# I2C_Keypad_host_module.net
KiCad netlist of a schematic drawn in Altium Designer
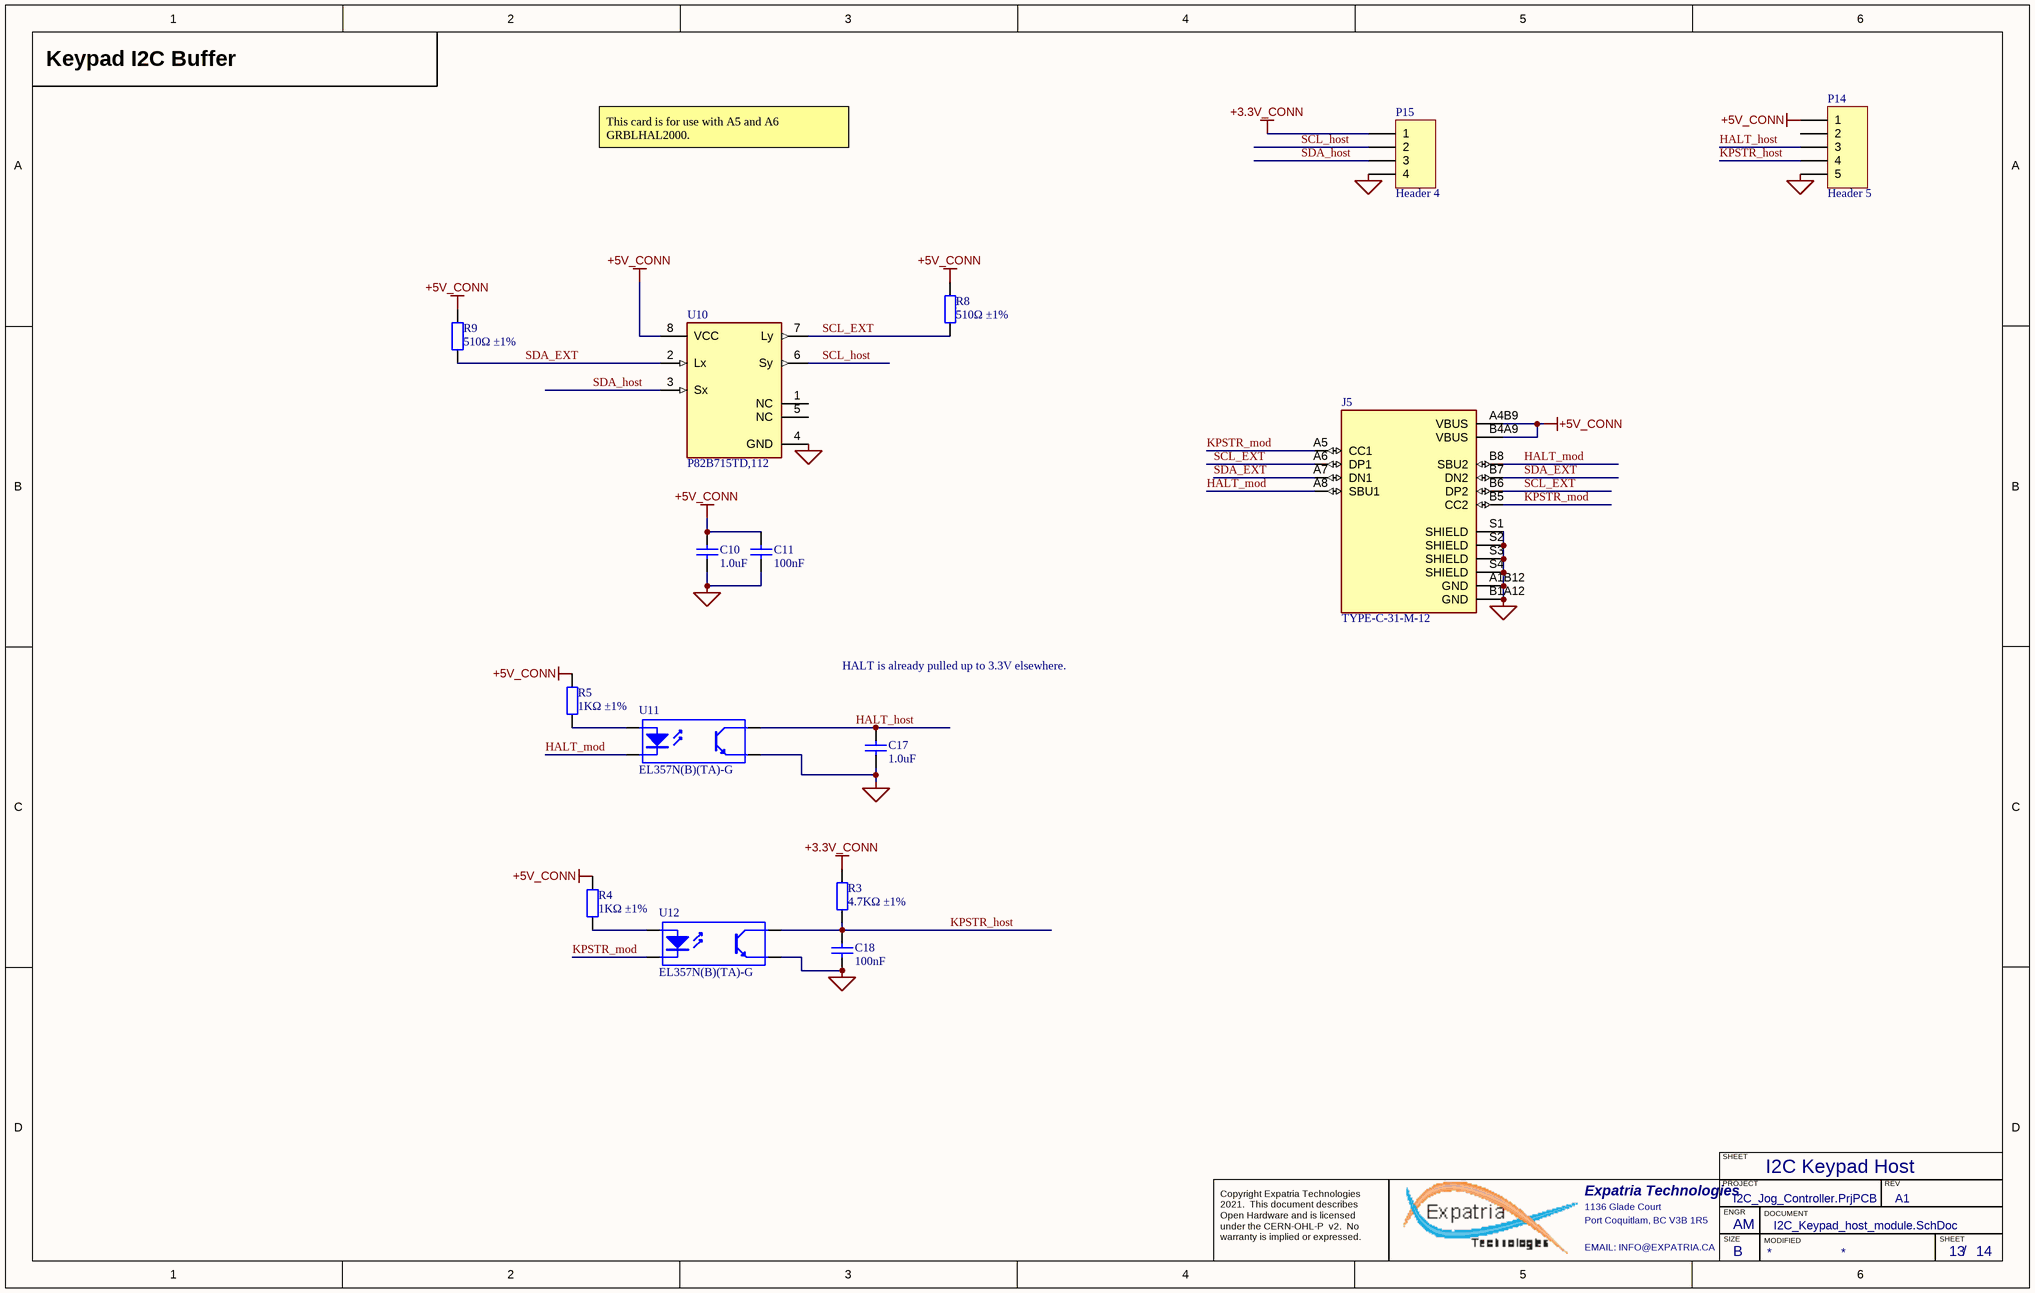
[diagram p0: I2C_Keypad_host_module.SchDoc]

(export (version "E")
  (design (tool "Eeschema 10.0.6"))
  (components
    (comp (ref "C10")
      (value "1.0uF")
      (footprint "0402_C")
      (description "Chip capacitor")
      (fields
        (field (name "MANUFACTURER") "Samsung Electro-Mechanics")
        (field (name "PARTNUMBER") "CL05A105KA5NQNC")
      )
      (libsource (lib "Cap") (part "0402 1.0uF (105) 10% 25V"))
    )
    (comp (ref "C11")
      (value "100nF")
      (footprint "0402_C")
      (description "Chip capacitors")
      (fields
        (field (name "MANUFACTURER") "Samsung Electro-Mechanics")
        (field (name "PARTNUMBER") "CL05B104KO5NNNC")
      )
      (libsource (lib "Cap") (part "0402 100nF (104) 10% 16V"))
    )
    (comp (ref "C17")
      (value "1.0uF")
      (footprint "0402_C")
      (description "Chip capacitor")
      (fields
        (field (name "MANUFACTURER") "Samsung Electro-Mechanics")
        (field (name "PARTNUMBER") "CL05A105KA5NQNC")
      )
      (libsource (lib "Cap") (part "0402 1.0uF (105) 10% 25V"))
    )
    (comp (ref "C18")
      (value "100nF")
      (footprint "0402_C")
      (description "Chip capacitors")
      (fields
        (field (name "MANUFACTURER") "Samsung Electro-Mechanics")
        (field (name "PARTNUMBER") "CL05B104KO5NNNC")
      )
      (libsource (lib "Cap") (part "0402 100nF (104) 10% 16V"))
    )
    (comp (ref "J5")
      (value "TYPE-C-31-M-12")
      (footprint "HRO_TYPE-C-31-M-12")
      (description "USB Connectors 24 Receptacle 1 8.94*7.3mm RoHS")
      (fields (field (name "MF") "HRO Electronics Co., Ltd."))
      (libsource (lib "Universal_CNC_Breakout") (part "TYPE-C-31-M-12"))
    )
    (comp (ref "P14")
      (value "Header 5")
      (footprint "HDR1X5")
      (description "Header, 5-Pin")
      (fields (field (name "PUBLISHER") "Altium Limited"))
      (libsource (lib "PrintNC_GRBLHAL_Breakout") (part "Header 5"))
    )
    (comp (ref "P15")
      (value "Header 4")
      (footprint "HDR1X4")
      (description "Header, 4-Pin")
      (fields (field (name "PUBLISHER") "Altium Limited"))
      (libsource (lib "PrintNC_GRBLHAL_Breakout") (part "Header 4"))
    )
    (comp (ref "R3")
      (value "4.7KΩ ±1%")
      (footprint "0402_R")
      (description "Chip resistor")
      (fields (field (name "MANUFACTURER") "Uniroyal Elec") (field (name "PARTNUMBER") "0402WGF4701TCE"))
      (libsource (lib "RES") (part "0402 4.7K (4701) 1%"))
    )
    (comp (ref "R4")
      (value "1KΩ ±1%")
      (footprint "0402_R")
      (description "Chip resistor")
      (fields (field (name "MANUFACTURER") "Uniroyal Elec") (field (name "PARTNUMBER") "0402WGF1001TCE"))
      (libsource (lib "RES") (part "0402 1K (1001) 1%"))
    )
    (comp (ref "R5")
      (value "1KΩ ±1%")
      (footprint "0402_R")
      (description "Chip resistor")
      (fields (field (name "MANUFACTURER") "Uniroyal Elec") (field (name "PARTNUMBER") "0402WGF1001TCE"))
      (libsource (lib "RES") (part "0402 1K (1001) 1%"))
    )
    (comp (ref "R8")
      (value "510Ω ±1%")
      (footprint "0402_R")
      (description "Chip resistor")
      (fields (field (name "MANUFACTURER") "Uniroyal Elec") (field (name "PARTNUMBER") "0402WGF5100TCE"))
      (libsource (lib "PrintNC_GRBLHAL_Breakout") (part "0402 510R (5100) 1%"))
    )
    (comp (ref "R9")
      (value "510Ω ±1%")
      (footprint "0402_R")
      (description "Chip resistor")
      (fields (field (name "MANUFACTURER") "Uniroyal Elec") (field (name "PARTNUMBER") "0402WGF5100TCE"))
      (libsource (lib "") (part "0402 510R (5100) 1%_1"))
    )
    (comp (ref "U10")
      (value "P82B715TD,112")
      (footprint "FP-SOT96-1-MFG")
      (description "IC REDRIVER I2C 1CH 400KHZ 8SO")
      (fields
        (field (name "MANUFACTURER") "NXP Semicon")
        (field (name "MANUFACTURER_PART_NUMBER") "P82B715TD,118")
      )
      (libsource (lib "Altium Content Vault") (part "feec727f4072afc4f94d4e12e138974"))
    )
    (comp (ref "U11")
      (value "EL357N(B)(TA)-G")
      (footprint "SOP-4_P2.54")
      (description "贴片光耦")
      (libsource (lib "IC") (part "EL357N(B)(TA)-G_[C6649]"))
    )
    (comp (ref "U12")
      (value "EL357N(B)(TA)-G")
      (footprint "SOP-4_P2.54")
      (description "贴片光耦")
      (libsource (lib "IC") (part "EL357N(B)(TA)-G_[C6649]"))
    )
  )
  (nets
    (net (code "1") (name "+3.3V_CONN") (class "Default")
      (node (ref "P15") (pin "1") (pinfunction "1_1") (pintype "passive"))
      (node (ref "R3") (pin "2") (pinfunction "2_2") (pintype "passive"))
    )
    (net (code "2") (name "+5V_CONN") (class "Default")
      (node (ref "C10") (pin "2") (pinfunction "2_2") (pintype "passive"))
      (node (ref "C11") (pin "2") (pinfunction "2_2") (pintype "passive"))
      (node (ref "J5") (pin "A4B9") (pinfunction "VBUS_A4B9") (pintype "power_in"))
      (node (ref "J5") (pin "B4A9") (pinfunction "VBUS_B4A9") (pintype "power_in"))
      (node (ref "P14") (pin "1") (pinfunction "1_1") (pintype "passive"))
      (node (ref "R4") (pin "1") (pinfunction "1_1") (pintype "passive"))
      (node (ref "R5") (pin "1") (pinfunction "1_1") (pintype "passive"))
      (node (ref "R8") (pin "2") (pinfunction "2_2") (pintype "passive"))
      (node (ref "R9") (pin "2") (pinfunction "2_2") (pintype "passive"))
      (node (ref "U10") (pin "8") (pinfunction "VCC_8") (pintype "power_in"))
    )
    (net (code "3") (name "/HALT_host") (class "Default")
      (node (ref "C17") (pin "2") (pinfunction "2_2") (pintype "passive"))
      (node (ref "P14") (pin "3") (pinfunction "3_3") (pintype "passive"))
      (node (ref "U11") (pin "4") (pinfunction "C_4") (pintype "passive"))
    )
    (net (code "4") (name "/HALT_mod") (class "Default")
      (node (ref "J5") (pin "A8") (pinfunction "SBU1_A8") (pintype "bidirectional"))
      (node (ref "J5") (pin "B8") (pinfunction "SBU2_B8") (pintype "bidirectional"))
      (node (ref "U11") (pin "2") (pinfunction "K_2") (pintype "passive"))
    )
    (net (code "5") (name "/KPSTR_host") (class "Default")
      (node (ref "C18") (pin "2") (pinfunction "2_2") (pintype "passive"))
      (node (ref "P14") (pin "4") (pinfunction "4_4") (pintype "passive"))
      (node (ref "R3") (pin "1") (pinfunction "1_1") (pintype "passive"))
      (node (ref "U12") (pin "4") (pinfunction "C_4") (pintype "passive"))
    )
    (net (code "6") (name "/KPSTR_mod") (class "Default")
      (node (ref "J5") (pin "A5") (pinfunction "CC1_A5") (pintype "bidirectional"))
      (node (ref "J5") (pin "B5") (pinfunction "CC2_B5") (pintype "bidirectional"))
      (node (ref "U12") (pin "2") (pinfunction "K_2") (pintype "passive"))
    )
    (net (code "7") (name "/SCL_EXT") (class "Default")
      (node (ref "J5") (pin "A6") (pinfunction "DP1_A6") (pintype "bidirectional"))
      (node (ref "J5") (pin "B6") (pinfunction "DP2_B6") (pintype "bidirectional"))
      (node (ref "R8") (pin "1") (pinfunction "1_1") (pintype "passive"))
      (node (ref "U10") (pin "7") (pinfunction "Ly_7") (pintype "output"))
    )
    (net (code "8") (name "/SCL_host") (class "Default")
      (node (ref "P15") (pin "2") (pinfunction "2_2") (pintype "passive"))
      (node (ref "U10") (pin "6") (pinfunction "Sy_6") (pintype "output"))
    )
    (net (code "9") (name "/SDA_EXT") (class "Default")
      (node (ref "J5") (pin "A7") (pinfunction "DN1_A7") (pintype "bidirectional"))
      (node (ref "J5") (pin "B7") (pinfunction "DN2_B7") (pintype "bidirectional"))
      (node (ref "R9") (pin "1") (pinfunction "1_1") (pintype "passive"))
      (node (ref "U10") (pin "2") (pinfunction "Lx_2") (pintype "input"))
    )
    (net (code "10") (name "/SDA_host") (class "Default")
      (node (ref "P15") (pin "3") (pinfunction "3_3") (pintype "passive"))
      (node (ref "U10") (pin "3") (pinfunction "Sx_3") (pintype "input"))
    )
    (net (code "11") (name "GND_CONN") (class "Default")
      (node (ref "C10") (pin "1") (pinfunction "1_1") (pintype "passive"))
      (node (ref "C11") (pin "1") (pinfunction "1_1") (pintype "passive"))
      (node (ref "C17") (pin "1") (pinfunction "1_1") (pintype "passive"))
      (node (ref "C18") (pin "1") (pinfunction "1_1") (pintype "passive"))
      (node (ref "J5") (pin "A1B12") (pinfunction "GND_A1B12") (pintype "power_in"))
      (node (ref "J5") (pin "B1A12") (pinfunction "GND_B1A12") (pintype "power_in"))
      (node (ref "J5") (pin "S1") (pinfunction "SHIELD_S1") (pintype "passive"))
      (node (ref "J5") (pin "S2") (pinfunction "SHIELD_S2") (pintype "passive"))
      (node (ref "J5") (pin "S3") (pinfunction "SHIELD_S3") (pintype "passive"))
      (node (ref "J5") (pin "S4") (pinfunction "SHIELD_S4") (pintype "passive"))
      (node (ref "P14") (pin "5") (pinfunction "5_5") (pintype "passive"))
      (node (ref "P15") (pin "4") (pinfunction "4_4") (pintype "passive"))
      (node (ref "U10") (pin "4") (pinfunction "GND_4") (pintype "power_in"))
      (node (ref "U11") (pin "3") (pinfunction "E_3") (pintype "passive"))
      (node (ref "U12") (pin "3") (pinfunction "E_3") (pintype "passive"))
    )
    (net (code "12") (name "Net-(U11-A)") (class "Default")
      (node (ref "R5") (pin "2") (pinfunction "2_2") (pintype "passive"))
      (node (ref "U11") (pin "1") (pinfunction "A_1") (pintype "passive"))
    )
    (net (code "13") (name "Net-(U12-A)") (class "Default")
      (node (ref "R4") (pin "2") (pinfunction "2_2") (pintype "passive"))
      (node (ref "U12") (pin "1") (pinfunction "A_1") (pintype "passive"))
    )
    (net (code "14") (name "unconnected-(P14-Pad2)") (class "Default")
      (node (ref "P14") (pin "2") (pinfunction "2_2") (pintype "passive"))
    )
    (net (code "15") (name "unconnected-(U10-NC-Pad1)") (class "Default")
      (node (ref "U10") (pin "1") (pinfunction "NC_1") (pintype "passive"))
    )
    (net (code "16") (name "unconnected-(U10-NC-Pad5)") (class "Default")
      (node (ref "U10") (pin "5") (pinfunction "NC_5") (pintype "passive"))
    )
  )
)
